# MiSTer_LLOAD_DIY_Edition.net
KiCad netlist of a schematic drawn in EAGLE
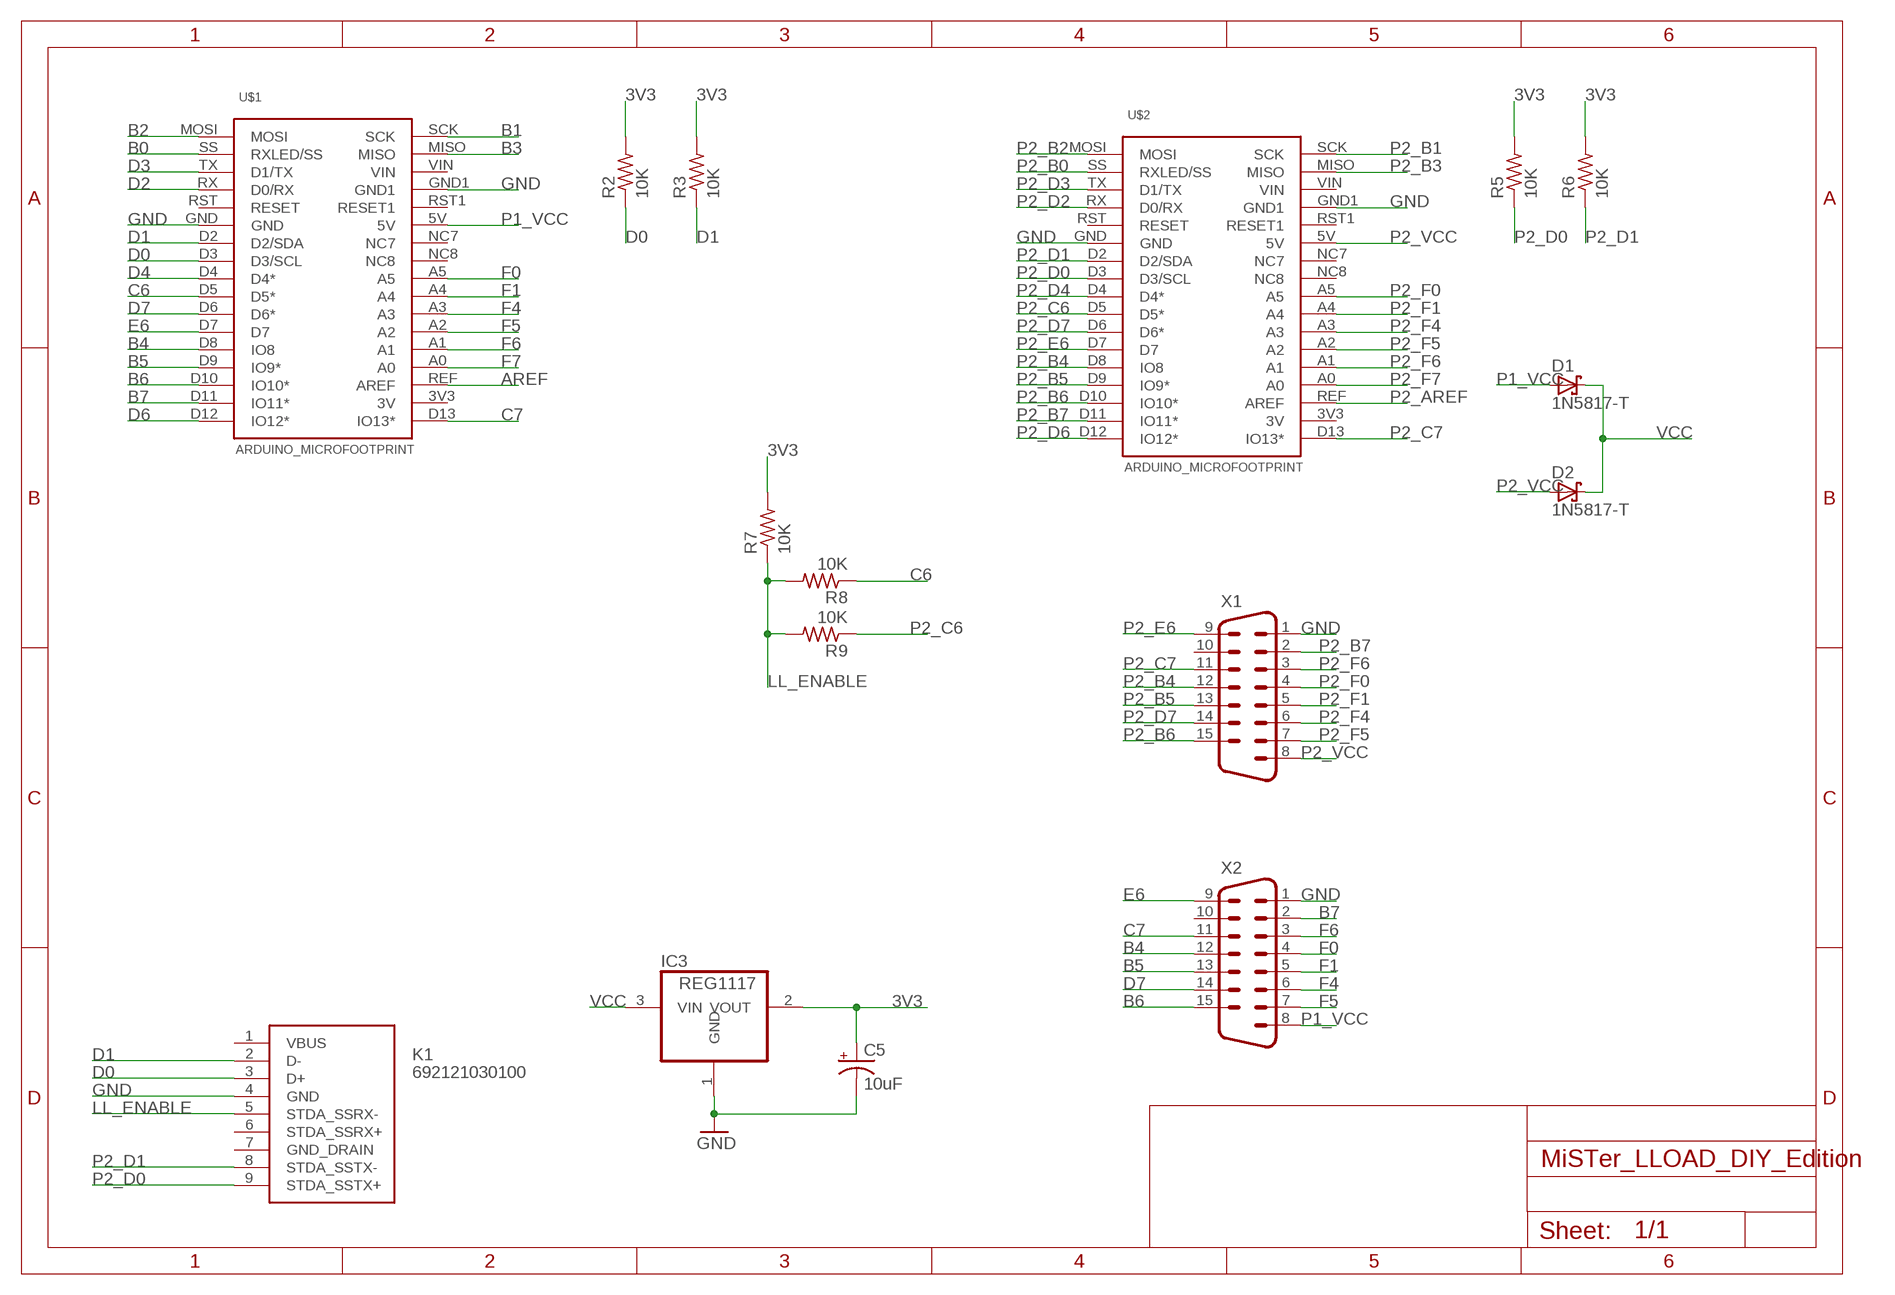
[diagram p0: schematic, sheet 1]

(export (version "E")
  (design (tool "Eeschema 10.0.6"))
  (components
    (comp (ref "C5")
      (value "10uF")
      (footprint "eagle-import:E2,5-6")
      (libsource (lib "eagle-import") (part "CPOL-USE2.5-6"))
    )
    (comp (ref "D1")
      (value "1N5817-T")
      (footprint "eagle-import:DO41-7.6")
      (libsource (lib "eagle-import") (part "1N5817-T"))
    )
    (comp (ref "D2")
      (value "1N5817-T")
      (footprint "eagle-import:DO41-7.6")
      (libsource (lib "eagle-import") (part "1N5817-T"))
    )
    (comp (ref "IC3")
      (value "REG1117")
      (footprint "eagle-import:SOT223")
      (libsource (lib "eagle-import") (part "REG1117"))
    )
    (comp (ref "K1")
      (value "692121030100")
      (footprint "eagle-import:692121030100")
      (libsource (lib "eagle-import") (part "692121030100"))
    )
    (comp (ref "R2")
      (value "10K")
      (footprint "eagle-import:0207_10")
      (libsource (lib "eagle-import") (part "R-US_0207/10"))
    )
    (comp (ref "R3")
      (value "10K")
      (footprint "eagle-import:0207_10")
      (libsource (lib "eagle-import") (part "R-US_0207/10"))
    )
    (comp (ref "R5")
      (value "10K")
      (footprint "eagle-import:0207_10")
      (libsource (lib "eagle-import") (part "R-US_0207/10"))
    )
    (comp (ref "R6")
      (value "10K")
      (footprint "eagle-import:0207_10")
      (libsource (lib "eagle-import") (part "R-US_0207/10"))
    )
    (comp (ref "R7")
      (value "10K")
      (footprint "eagle-import:0207_10")
      (libsource (lib "eagle-import") (part "R-US_0207/10"))
    )
    (comp (ref "R8")
      (value "10K")
      (footprint "eagle-import:0207_10")
      (libsource (lib "eagle-import") (part "R-US_0207/10"))
    )
    (comp (ref "R9")
      (value "10K")
      (footprint "eagle-import:0207_10")
      (libsource (lib "eagle-import") (part "R-US_0207/10"))
    )
    (comp (ref "U$1")
      (value "ARDUINO_MICROFOOTPRINT")
      (footprint "eagle-import:ARDUINO-MICRO")
      (libsource (lib "eagle-import") (part "ARDUINO_MICROFOOTPRINT"))
    )
    (comp (ref "U$2")
      (value "ARDUINO_MICROFOOTPRINT")
      (footprint "eagle-import:ARDUINO-MICRO")
      (libsource (lib "eagle-import") (part "ARDUINO_MICROFOOTPRINT"))
    )
    (comp (ref "X1")
      (value "M15HP")
      (footprint "eagle-import:M15HP")
      (libsource (lib "eagle-import") (part "M15HP"))
    )
    (comp (ref "X2")
      (value "M15HP")
      (footprint "eagle-import:M15HP")
      (libsource (lib "eagle-import") (part "M15HP"))
    )
  )
  (nets
    (net (code "1") (name "/3V3") (class "Default")
      (node (ref "C5") (pin "+") (pinfunction "+_+") (pintype "passive"))
      (node (ref "IC3") (pin "2") (pinfunction "VOUT_2") (pintype "output"))
      (node (ref "R2") (pin "2") (pinfunction "2_2") (pintype "passive"))
      (node (ref "R3") (pin "2") (pinfunction "2_2") (pintype "passive"))
      (node (ref "R5") (pin "2") (pinfunction "2_2") (pintype "passive"))
      (node (ref "R6") (pin "2") (pinfunction "2_2") (pintype "passive"))
      (node (ref "R7") (pin "2") (pinfunction "2_2") (pintype "passive"))
    )
    (net (code "2") (name "/AREF") (class "Default")
      (node (ref "U$1") (pin "REF") (pinfunction "AREF_REF") (pintype "bidirectional"))
    )
    (net (code "3") (name "/B0") (class "Default")
      (node (ref "U$1") (pin "SS") (pinfunction "RXLED/SS_SS") (pintype "bidirectional"))
    )
    (net (code "4") (name "/B1") (class "Default")
      (node (ref "U$1") (pin "SCK") (pinfunction "SCK_SCK") (pintype "bidirectional"))
    )
    (net (code "5") (name "/B2") (class "Default")
      (node (ref "U$1") (pin "MOSI") (pinfunction "MOSI_MOSI") (pintype "bidirectional"))
    )
    (net (code "6") (name "/B3") (class "Default")
      (node (ref "U$1") (pin "MISO") (pinfunction "MISO_MISO") (pintype "bidirectional"))
    )
    (net (code "7") (name "/B4") (class "Default")
      (node (ref "U$1") (pin "D8") (pinfunction "IO8_D8") (pintype "bidirectional"))
      (node (ref "X2") (pin "12") (pinfunction "12_12") (pintype "passive"))
    )
    (net (code "8") (name "/B5") (class "Default")
      (node (ref "U$1") (pin "D9") (pinfunction "IO9*_D9") (pintype "bidirectional"))
      (node (ref "X2") (pin "13") (pinfunction "13_13") (pintype "passive"))
    )
    (net (code "9") (name "/B6") (class "Default")
      (node (ref "U$1") (pin "D10") (pinfunction "IO10*_D10") (pintype "bidirectional"))
      (node (ref "X2") (pin "15") (pinfunction "15_15") (pintype "passive"))
    )
    (net (code "10") (name "/B7") (class "Default")
      (node (ref "U$1") (pin "D11") (pinfunction "IO11*_D11") (pintype "bidirectional"))
      (node (ref "X2") (pin "2") (pinfunction "2_2") (pintype "passive"))
    )
    (net (code "11") (name "/C6") (class "Default")
      (node (ref "R8") (pin "1") (pinfunction "1_1") (pintype "passive"))
      (node (ref "U$1") (pin "D5") (pinfunction "D5*_D5") (pintype "bidirectional"))
    )
    (net (code "12") (name "/C7") (class "Default")
      (node (ref "U$1") (pin "D13") (pinfunction "IO13*_D13") (pintype "bidirectional"))
      (node (ref "X2") (pin "11") (pinfunction "11_11") (pintype "passive"))
    )
    (net (code "13") (name "/D0") (class "Default")
      (node (ref "K1") (pin "3") (pinfunction "D+_3") (pintype "bidirectional"))
      (node (ref "R2") (pin "1") (pinfunction "1_1") (pintype "passive"))
      (node (ref "U$1") (pin "D3") (pinfunction "D3/SCL_D3") (pintype "bidirectional"))
    )
    (net (code "14") (name "/D1") (class "Default")
      (node (ref "K1") (pin "2") (pinfunction "D-_2") (pintype "bidirectional"))
      (node (ref "R3") (pin "1") (pinfunction "1_1") (pintype "passive"))
      (node (ref "U$1") (pin "D2") (pinfunction "D2/SDA_D2") (pintype "bidirectional"))
    )
    (net (code "15") (name "/D2") (class "Default")
      (node (ref "U$1") (pin "RX") (pinfunction "D0/RX_RX") (pintype "bidirectional"))
    )
    (net (code "16") (name "/D3") (class "Default")
      (node (ref "U$1") (pin "TX") (pinfunction "D1/TX_TX") (pintype "bidirectional"))
    )
    (net (code "17") (name "/D4") (class "Default")
      (node (ref "U$1") (pin "D4") (pinfunction "D4*_D4") (pintype "bidirectional"))
    )
    (net (code "18") (name "/D6") (class "Default")
      (node (ref "U$1") (pin "D12") (pinfunction "IO12*_D12") (pintype "bidirectional"))
    )
    (net (code "19") (name "/D7") (class "Default")
      (node (ref "U$1") (pin "D6") (pinfunction "D6*_D6") (pintype "bidirectional"))
      (node (ref "X2") (pin "14") (pinfunction "14_14") (pintype "passive"))
    )
    (net (code "20") (name "/E6") (class "Default")
      (node (ref "U$1") (pin "D7") (pinfunction "D7_D7") (pintype "bidirectional"))
      (node (ref "X2") (pin "9") (pinfunction "9_9") (pintype "passive"))
    )
    (net (code "21") (name "/F0") (class "Default")
      (node (ref "U$1") (pin "A5") (pinfunction "A5_A5") (pintype "bidirectional"))
      (node (ref "X2") (pin "4") (pinfunction "4_4") (pintype "passive"))
    )
    (net (code "22") (name "/F1") (class "Default")
      (node (ref "U$1") (pin "A4") (pinfunction "A4_A4") (pintype "bidirectional"))
      (node (ref "X2") (pin "5") (pinfunction "5_5") (pintype "passive"))
    )
    (net (code "23") (name "/F4") (class "Default")
      (node (ref "U$1") (pin "A3") (pinfunction "A3_A3") (pintype "bidirectional"))
      (node (ref "X2") (pin "6") (pinfunction "6_6") (pintype "passive"))
    )
    (net (code "24") (name "/F5") (class "Default")
      (node (ref "U$1") (pin "A2") (pinfunction "A2_A2") (pintype "bidirectional"))
      (node (ref "X2") (pin "7") (pinfunction "7_7") (pintype "passive"))
    )
    (net (code "25") (name "/F6") (class "Default")
      (node (ref "U$1") (pin "A1") (pinfunction "A1_A1") (pintype "bidirectional"))
      (node (ref "X2") (pin "3") (pinfunction "3_3") (pintype "passive"))
    )
    (net (code "26") (name "/F7") (class "Default")
      (node (ref "U$1") (pin "A0") (pinfunction "A0_A0") (pintype "bidirectional"))
    )
    (net (code "27") (name "/LL_ENABLE") (class "Default")
      (node (ref "K1") (pin "5") (pinfunction "STDA_SSRX-_5") (pintype "bidirectional"))
      (node (ref "R7") (pin "1") (pinfunction "1_1") (pintype "passive"))
      (node (ref "R8") (pin "2") (pinfunction "2_2") (pintype "passive"))
      (node (ref "R9") (pin "2") (pinfunction "2_2") (pintype "passive"))
    )
    (net (code "28") (name "/P1_VCC") (class "Default")
      (node (ref "D1") (pin "A") (pinfunction "A_A") (pintype "passive"))
      (node (ref "U$1") (pin "5V") (pinfunction "5V_5V") (pintype "bidirectional"))
      (node (ref "X2") (pin "8") (pinfunction "8_8") (pintype "passive"))
    )
    (net (code "29") (name "/P2_AREF") (class "Default")
      (node (ref "U$2") (pin "REF") (pinfunction "AREF_REF") (pintype "bidirectional"))
    )
    (net (code "30") (name "/P2_B0") (class "Default")
      (node (ref "U$2") (pin "SS") (pinfunction "RXLED/SS_SS") (pintype "bidirectional"))
    )
    (net (code "31") (name "/P2_B1") (class "Default")
      (node (ref "U$2") (pin "SCK") (pinfunction "SCK_SCK") (pintype "bidirectional"))
    )
    (net (code "32") (name "/P2_B2") (class "Default")
      (node (ref "U$2") (pin "MOSI") (pinfunction "MOSI_MOSI") (pintype "bidirectional"))
    )
    (net (code "33") (name "/P2_B3") (class "Default")
      (node (ref "U$2") (pin "MISO") (pinfunction "MISO_MISO") (pintype "bidirectional"))
    )
    (net (code "34") (name "/P2_B4") (class "Default")
      (node (ref "U$2") (pin "D8") (pinfunction "IO8_D8") (pintype "bidirectional"))
      (node (ref "X1") (pin "12") (pinfunction "12_12") (pintype "passive"))
    )
    (net (code "35") (name "/P2_B5") (class "Default")
      (node (ref "U$2") (pin "D9") (pinfunction "IO9*_D9") (pintype "bidirectional"))
      (node (ref "X1") (pin "13") (pinfunction "13_13") (pintype "passive"))
    )
    (net (code "36") (name "/P2_B6") (class "Default")
      (node (ref "U$2") (pin "D10") (pinfunction "IO10*_D10") (pintype "bidirectional"))
      (node (ref "X1") (pin "15") (pinfunction "15_15") (pintype "passive"))
    )
    (net (code "37") (name "/P2_B7") (class "Default")
      (node (ref "U$2") (pin "D11") (pinfunction "IO11*_D11") (pintype "bidirectional"))
      (node (ref "X1") (pin "2") (pinfunction "2_2") (pintype "passive"))
    )
    (net (code "38") (name "/P2_C6") (class "Default")
      (node (ref "R9") (pin "1") (pinfunction "1_1") (pintype "passive"))
      (node (ref "U$2") (pin "D5") (pinfunction "D5*_D5") (pintype "bidirectional"))
    )
    (net (code "39") (name "/P2_C7") (class "Default")
      (node (ref "U$2") (pin "D13") (pinfunction "IO13*_D13") (pintype "bidirectional"))
      (node (ref "X1") (pin "11") (pinfunction "11_11") (pintype "passive"))
    )
    (net (code "40") (name "/P2_D0") (class "Default")
      (node (ref "K1") (pin "9") (pinfunction "STDA_SSTX+_9") (pintype "bidirectional"))
      (node (ref "R5") (pin "1") (pinfunction "1_1") (pintype "passive"))
      (node (ref "U$2") (pin "D3") (pinfunction "D3/SCL_D3") (pintype "bidirectional"))
    )
    (net (code "41") (name "/P2_D1") (class "Default")
      (node (ref "K1") (pin "8") (pinfunction "STDA_SSTX-_8") (pintype "bidirectional"))
      (node (ref "R6") (pin "1") (pinfunction "1_1") (pintype "passive"))
      (node (ref "U$2") (pin "D2") (pinfunction "D2/SDA_D2") (pintype "bidirectional"))
    )
    (net (code "42") (name "/P2_D2") (class "Default")
      (node (ref "U$2") (pin "RX") (pinfunction "D0/RX_RX") (pintype "bidirectional"))
    )
    (net (code "43") (name "/P2_D3") (class "Default")
      (node (ref "U$2") (pin "TX") (pinfunction "D1/TX_TX") (pintype "bidirectional"))
    )
    (net (code "44") (name "/P2_D4") (class "Default")
      (node (ref "U$2") (pin "D4") (pinfunction "D4*_D4") (pintype "bidirectional"))
    )
    (net (code "45") (name "/P2_D6") (class "Default")
      (node (ref "U$2") (pin "D12") (pinfunction "IO12*_D12") (pintype "bidirectional"))
    )
    (net (code "46") (name "/P2_D7") (class "Default")
      (node (ref "U$2") (pin "D6") (pinfunction "D6*_D6") (pintype "bidirectional"))
      (node (ref "X1") (pin "14") (pinfunction "14_14") (pintype "passive"))
    )
    (net (code "47") (name "/P2_E6") (class "Default")
      (node (ref "U$2") (pin "D7") (pinfunction "D7_D7") (pintype "bidirectional"))
      (node (ref "X1") (pin "9") (pinfunction "9_9") (pintype "passive"))
    )
    (net (code "48") (name "/P2_F0") (class "Default")
      (node (ref "U$2") (pin "A5") (pinfunction "A5_A5") (pintype "bidirectional"))
      (node (ref "X1") (pin "4") (pinfunction "4_4") (pintype "passive"))
    )
    (net (code "49") (name "/P2_F1") (class "Default")
      (node (ref "U$2") (pin "A4") (pinfunction "A4_A4") (pintype "bidirectional"))
      (node (ref "X1") (pin "5") (pinfunction "5_5") (pintype "passive"))
    )
    (net (code "50") (name "/P2_F4") (class "Default")
      (node (ref "U$2") (pin "A3") (pinfunction "A3_A3") (pintype "bidirectional"))
      (node (ref "X1") (pin "6") (pinfunction "6_6") (pintype "passive"))
    )
    (net (code "51") (name "/P2_F5") (class "Default")
      (node (ref "U$2") (pin "A2") (pinfunction "A2_A2") (pintype "bidirectional"))
      (node (ref "X1") (pin "7") (pinfunction "7_7") (pintype "passive"))
    )
    (net (code "52") (name "/P2_F6") (class "Default")
      (node (ref "U$2") (pin "A1") (pinfunction "A1_A1") (pintype "bidirectional"))
      (node (ref "X1") (pin "3") (pinfunction "3_3") (pintype "passive"))
    )
    (net (code "53") (name "/P2_F7") (class "Default")
      (node (ref "U$2") (pin "A0") (pinfunction "A0_A0") (pintype "bidirectional"))
    )
    (net (code "54") (name "/P2_VCC") (class "Default")
      (node (ref "D2") (pin "A") (pinfunction "A_A") (pintype "passive"))
      (node (ref "U$2") (pin "5V") (pinfunction "5V_5V") (pintype "bidirectional"))
      (node (ref "X1") (pin "8") (pinfunction "8_8") (pintype "passive"))
    )
    (net (code "55") (name "/VCC") (class "Default")
      (node (ref "D1") (pin "C") (pinfunction "C_C") (pintype "passive"))
      (node (ref "D2") (pin "C") (pinfunction "C_C") (pintype "passive"))
      (node (ref "IC3") (pin "3") (pinfunction "VIN_3") (pintype "input"))
    )
    (net (code "56") (name "GND") (class "Default")
      (node (ref "C5") (pin "-") (pinfunction "-_-") (pintype "passive"))
      (node (ref "IC3") (pin "1") (pinfunction "GND_1") (pintype "power_in"))
      (node (ref "K1") (pin "4") (pinfunction "GND_4") (pintype "bidirectional"))
      (node (ref "U$1") (pin "GND") (pinfunction "GND_GND") (pintype "bidirectional"))
      (node (ref "U$1") (pin "GND1") (pinfunction "GND1_GND1") (pintype "bidirectional"))
      (node (ref "U$2") (pin "GND") (pinfunction "GND_GND") (pintype "bidirectional"))
      (node (ref "U$2") (pin "GND1") (pinfunction "GND1_GND1") (pintype "bidirectional"))
      (node (ref "X1") (pin "1") (pinfunction "1_1") (pintype "passive"))
      (node (ref "X2") (pin "1") (pinfunction "1_1") (pintype "passive"))
    )
    (net (code "57") (name "unconnected-(K1-GND_DRAIN-Pad7)") (class "Default")
      (node (ref "K1") (pin "7") (pinfunction "GND_DRAIN_7") (pintype "bidirectional"))
    )
    (net (code "58") (name "unconnected-(K1-STDA_SSRX+-Pad6)") (class "Default")
      (node (ref "K1") (pin "6") (pinfunction "STDA_SSRX+_6") (pintype "bidirectional"))
    )
    (net (code "59") (name "unconnected-(K1-VBUS-Pad1)") (class "Default")
      (node (ref "K1") (pin "1") (pinfunction "VBUS_1") (pintype "bidirectional"))
    )
    (net (code "60") (name "unconnected-(U$1-3V-Pad3V3)") (class "Default")
      (node (ref "U$1") (pin "3V3") (pinfunction "3V_3V3") (pintype "bidirectional"))
    )
    (net (code "61") (name "unconnected-(U$1-PadNC7)") (class "Default")
      (node (ref "U$1") (pin "NC7") (pinfunction "NC7_NC7") (pintype "bidirectional"))
    )
    (net (code "62") (name "unconnected-(U$1-PadNC8)") (class "Default")
      (node (ref "U$1") (pin "NC8") (pinfunction "NC8_NC8") (pintype "bidirectional"))
    )
    (net (code "63") (name "unconnected-(U$1-PadVIN)") (class "Default")
      (node (ref "U$1") (pin "VIN") (pinfunction "VIN_VIN") (pintype "bidirectional"))
    )
    (net (code "64") (name "unconnected-(U$1-RESET-PadRST)") (class "Default")
      (node (ref "U$1") (pin "RST") (pinfunction "RESET_RST") (pintype "bidirectional"))
    )
    (net (code "65") (name "unconnected-(U$1-RESET1-PadRST1)") (class "Default")
      (node (ref "U$1") (pin "RST1") (pinfunction "RESET1_RST1") (pintype "bidirectional"))
    )
    (net (code "66") (name "unconnected-(U$2-3V-Pad3V3)") (class "Default")
      (node (ref "U$2") (pin "3V3") (pinfunction "3V_3V3") (pintype "bidirectional"))
    )
    (net (code "67") (name "unconnected-(U$2-PadNC7)") (class "Default")
      (node (ref "U$2") (pin "NC7") (pinfunction "NC7_NC7") (pintype "bidirectional"))
    )
    (net (code "68") (name "unconnected-(U$2-PadNC8)") (class "Default")
      (node (ref "U$2") (pin "NC8") (pinfunction "NC8_NC8") (pintype "bidirectional"))
    )
    (net (code "69") (name "unconnected-(U$2-PadVIN)") (class "Default")
      (node (ref "U$2") (pin "VIN") (pinfunction "VIN_VIN") (pintype "bidirectional"))
    )
    (net (code "70") (name "unconnected-(U$2-RESET-PadRST)") (class "Default")
      (node (ref "U$2") (pin "RST") (pinfunction "RESET_RST") (pintype "bidirectional"))
    )
    (net (code "71") (name "unconnected-(U$2-RESET1-PadRST1)") (class "Default")
      (node (ref "U$2") (pin "RST1") (pinfunction "RESET1_RST1") (pintype "bidirectional"))
    )
    (net (code "72") (name "unconnected-(X1-Pad10)") (class "Default")
      (node (ref "X1") (pin "10") (pinfunction "10_10") (pintype "passive"))
    )
    (net (code "73") (name "unconnected-(X2-Pad10)") (class "Default")
      (node (ref "X2") (pin "10") (pinfunction "10_10") (pintype "passive"))
    )
  )
)
